# UBX_NORA_B1_SCHEM_0004_Interface_MCU.net
KiCad netlist of a schematic drawn in Altium Designer
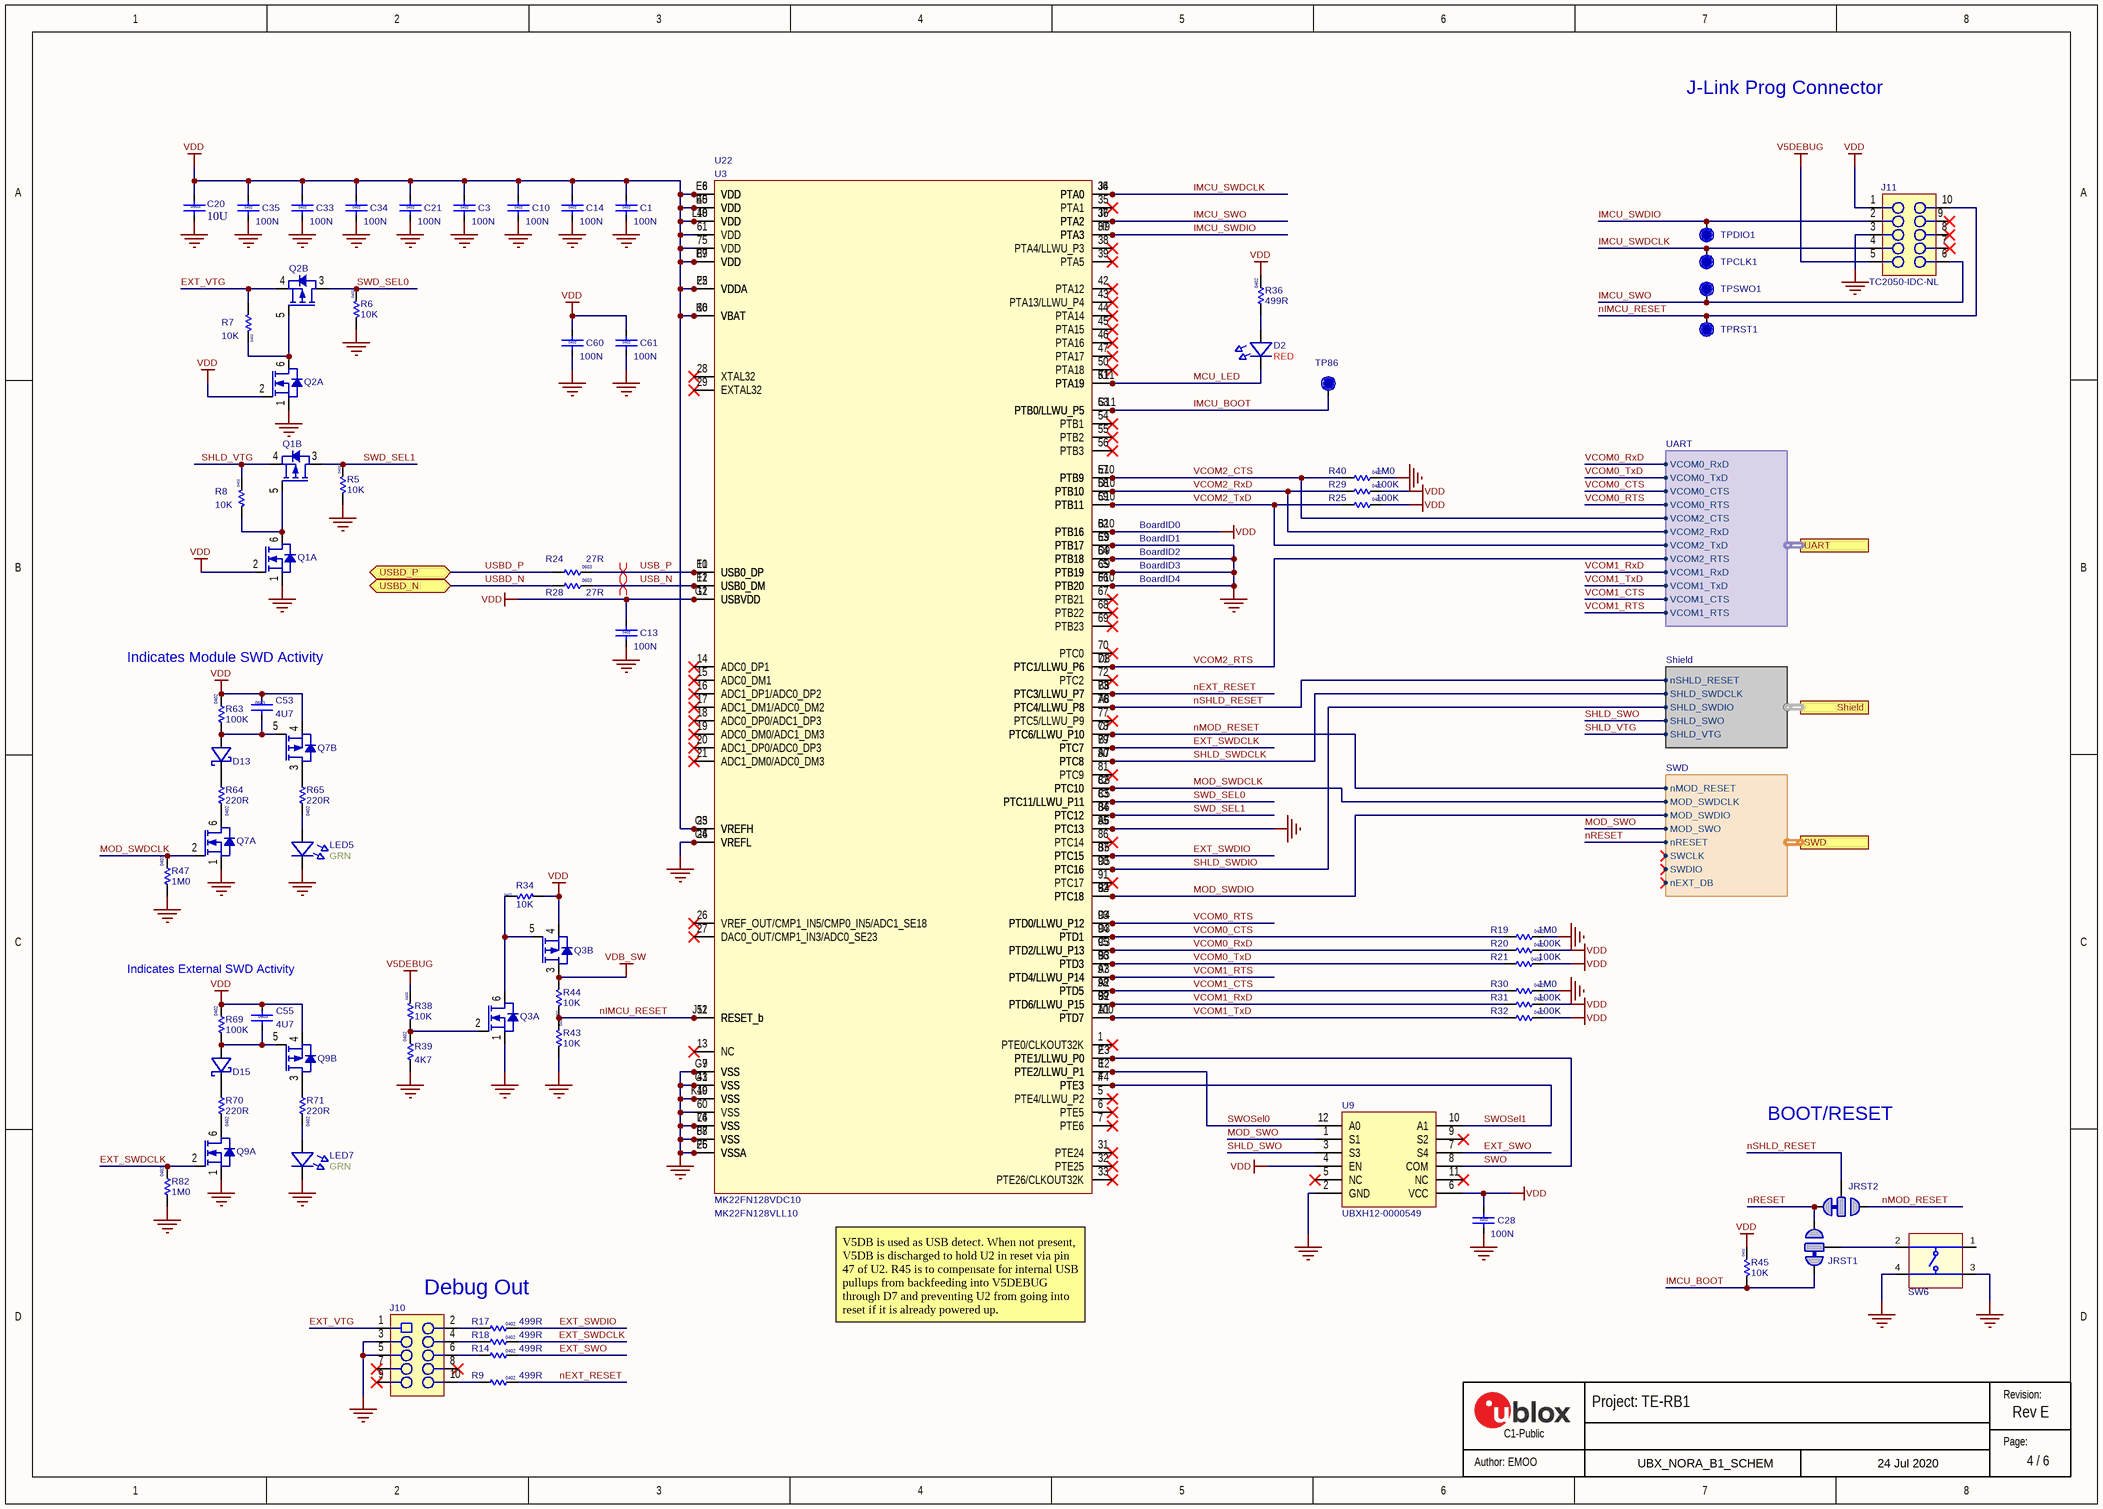
[diagram p0: UBX_NORA_B1_SCHEM_0004_Interface_MCU.SchDoc]

(export (version "E")
  (design (tool "Eeschema 10.0.6"))
  (components
    (comp (ref "C1")
      (value "100N")
      (footprint "Cap 0402 HD")
      (description "CAP CER X5R 0402 100N 10% 10V")
      (fields
        (field (name "SIZE") "0402")
        (field (name "PART NUMBER") "UBXH01-2021002")
        (field (name "TOLERANCE") "10%")
        (field (name "EDITOR") "roland.rust")
        (field (name "RELEASED BY") "roland.rust")
      )
      (libsource (lib "UBX_Parts_DB_Lib") (part "Cap Chip"))
    )
    (comp (ref "C3")
      (value "100N")
      (footprint "Cap 0402 HD")
      (description "CAP CER X5R 0402 100N 10% 10V")
      (fields
        (field (name "SIZE") "0402")
        (field (name "PART NUMBER") "UBXH01-2021002")
        (field (name "TOLERANCE") "10%")
        (field (name "EDITOR") "roland.rust")
        (field (name "RELEASED BY") "roland.rust")
      )
      (libsource (lib "UBX_Parts_DB_Lib") (part "Cap Chip"))
    )
    (comp (ref "C10")
      (value "100N")
      (footprint "Cap 0402 HD")
      (description "CAP CER X5R 0402 100N 10% 10V")
      (fields
        (field (name "SIZE") "0402")
        (field (name "PART NUMBER") "UBXH01-2021002")
        (field (name "TOLERANCE") "10%")
        (field (name "EDITOR") "roland.rust")
        (field (name "RELEASED BY") "roland.rust")
      )
      (libsource (lib "UBX_Parts_DB_Lib") (part "Cap Chip"))
    )
    (comp (ref "C13")
      (value "100N")
      (footprint "Cap 0402 HD")
      (description "CAP CER X5R 0402 100N 10% 10V")
      (fields
        (field (name "SIZE") "0402")
        (field (name "PART NUMBER") "UBXH01-2021002")
        (field (name "TOLERANCE") "10%")
        (field (name "EDITOR") "roland.rust")
        (field (name "RELEASED BY") "roland.rust")
      )
      (libsource (lib "UBX_Parts_DB_Lib") (part "Cap Chip"))
    )
    (comp (ref "C14")
      (value "100N")
      (footprint "Cap 0402 HD")
      (description "CAP CER X5R 0402 100N 10% 10V")
      (fields
        (field (name "SIZE") "0402")
        (field (name "PART NUMBER") "UBXH01-2021002")
        (field (name "TOLERANCE") "10%")
        (field (name "EDITOR") "roland.rust")
        (field (name "RELEASED BY") "roland.rust")
      )
      (libsource (lib "UBX_Parts_DB_Lib") (part "Cap Chip"))
    )
    (comp (ref "C20")
      (value "10U")
      (footprint "CAP 0603 HD")
      (description "CAP CER X5R 0603 10U 20% 10V")
      (fields
        (field (name "SIZE") "0603")
        (field (name "PART NUMBER") "UBXH01-0000040")
        (field (name "TOLERANCE") "20%")
        (field (name "EDITOR") "pierpaolo.arban")
        (field (name "RELEASED BY") "matej.budin")
      )
      (libsource (lib "UBX_Parts_DB_Lib") (part "Cap Chip"))
    )
    (comp (ref "C21")
      (value "100N")
      (footprint "Cap 0402 HD")
      (description "CAP CER X5R 0402 100N 10% 10V")
      (fields
        (field (name "SIZE") "0402")
        (field (name "PART NUMBER") "UBXH01-2021002")
        (field (name "TOLERANCE") "10%")
        (field (name "EDITOR") "roland.rust")
        (field (name "RELEASED BY") "roland.rust")
      )
      (libsource (lib "UBX_Parts_DB_Lib") (part "Cap Chip"))
    )
    (comp (ref "C28")
      (value "100N")
      (footprint "Cap 0402 HD")
      (description "CAP CER X5R 0402 100N 10% 10V")
      (fields
        (field (name "SIZE") "0402")
        (field (name "PART NUMBER") "UBXH01-2021002")
        (field (name "TOLERANCE") "10%")
        (field (name "EDITOR") "roland.rust")
        (field (name "RELEASED BY") "roland.rust")
      )
      (libsource (lib "UBX_Parts_DB_Lib") (part "Cap Chip"))
    )
    (comp (ref "C33")
      (value "100N")
      (footprint "Cap 0402 HD")
      (description "CAP CER X5R 0402 100N 10% 10V")
      (fields
        (field (name "SIZE") "0402")
        (field (name "PART NUMBER") "UBXH01-2021002")
        (field (name "TOLERANCE") "10%")
        (field (name "EDITOR") "roland.rust")
        (field (name "RELEASED BY") "roland.rust")
      )
      (libsource (lib "UBX_Parts_DB_Lib") (part "Cap Chip"))
    )
    (comp (ref "C34")
      (value "100N")
      (footprint "Cap 0402 HD")
      (description "CAP CER X5R 0402 100N 10% 10V")
      (fields
        (field (name "SIZE") "0402")
        (field (name "PART NUMBER") "UBXH01-2021002")
        (field (name "TOLERANCE") "10%")
        (field (name "EDITOR") "roland.rust")
        (field (name "RELEASED BY") "roland.rust")
      )
      (libsource (lib "UBX_Parts_DB_Lib") (part "Cap Chip"))
    )
    (comp (ref "C35")
      (value "100N")
      (footprint "Cap 0402 HD")
      (description "CAP CER X5R 0402 100N 10% 10V")
      (fields
        (field (name "SIZE") "0402")
        (field (name "PART NUMBER") "UBXH01-2021002")
        (field (name "TOLERANCE") "10%")
        (field (name "EDITOR") "roland.rust")
        (field (name "RELEASED BY") "roland.rust")
      )
      (libsource (lib "UBX_Parts_DB_Lib") (part "Cap Chip"))
    )
    (comp (ref "C53")
      (value "4U7")
      (footprint "CAP 0603 HD")
      (description "CAP CER X5R 0603 4U7 10% 6.3V")
      (fields
        (field (name "SIZE") "0603")
        (field (name "PART NUMBER") "UBXH01-2002003")
        (field (name "TOLERANCE") "10%")
        (field (name "EDITOR") "philippe.largier")
        (field (name "RELEASED BY") "roland.rust")
      )
      (libsource (lib "UBX_Parts_DB_Lib") (part "Cap Chip"))
    )
    (comp (ref "C55")
      (value "4U7")
      (footprint "CAP 0603 HD")
      (description "CAP CER X5R 0603 4U7 10% 6.3V")
      (fields
        (field (name "SIZE") "0603")
        (field (name "PART NUMBER") "UBXH01-2002003")
        (field (name "TOLERANCE") "10%")
        (field (name "EDITOR") "philippe.largier")
        (field (name "RELEASED BY") "roland.rust")
      )
      (libsource (lib "UBX_Parts_DB_Lib") (part "Cap Chip"))
    )
    (comp (ref "C60")
      (value "100N")
      (footprint "Cap 0402 HD")
      (description "CAP CER X5R 0402 100N 10% 10V")
      (fields
        (field (name "SIZE") "0402")
        (field (name "PART NUMBER") "UBXH01-2021002")
        (field (name "TOLERANCE") "10%")
        (field (name "EDITOR") "roland.rust")
        (field (name "RELEASED BY") "roland.rust")
      )
      (libsource (lib "UBX_Parts_DB_Lib") (part "Cap Chip"))
    )
    (comp (ref "C61")
      (value "100N")
      (footprint "Cap 0402 HD")
      (description "CAP CER X5R 0402 100N 10% 10V")
      (fields
        (field (name "SIZE") "0402")
        (field (name "PART NUMBER") "UBXH01-2021002")
        (field (name "TOLERANCE") "10%")
        (field (name "EDITOR") "roland.rust")
        (field (name "RELEASED BY") "roland.rust")
      )
      (libsource (lib "UBX_Parts_DB_Lib") (part "Cap Chip"))
    )
    (comp (ref "D2")
      (value "UBXH11-0000000")
      (footprint "LED_0603_RED")
      (description "LED SMD 0603 ULTRABRIGHT LITE-ON LTST-C190KRKT RED 30mA")
      (fields
        (field (name "COLOR") "RED")
        (field (name "MANUFACTURER") "Lite-on Technology Corporation")
        (field (name "EDITOR") "massimo.vlacci")
        (field (name "RELEASED BY") "sandro.sestan")
      )
      (libsource (lib "UBX_Parts_DB_Lib") (part "LED_BASE"))
    )
    (comp (ref "D13")
      (value "UBXH07-0000039")
      (footprint "SOD-523")
      (description "SCHOTTKY BARRIER DIODE 30V 200mA")
      (fields
        (field (name "MANUFACTURER") "ON Semiconductor")
        (field (name "EDITOR") "matej.budin")
        (field (name "RELEASED BY") "pierpaolo.arban")
      )
      (libsource (lib "UBX_Parts_DB_Lib") (part "Diode_Schottky"))
    )
    (comp (ref "D15")
      (value "UBXH07-0000039")
      (footprint "SOD-523")
      (description "SCHOTTKY BARRIER DIODE 30V 200mA")
      (fields
        (field (name "MANUFACTURER") "ON Semiconductor")
        (field (name "EDITOR") "matej.budin")
        (field (name "RELEASED BY") "pierpaolo.arban")
      )
      (libsource (lib "UBX_Parts_DB_Lib") (part "Diode_Schottky"))
    )
    (comp (ref "J10")
      (value "UBXH04-0000194")
      (footprint "FTSH-105-01-F-DV-K")
      (description "2-ROW SMD-PCB CONN 50MIL GRID 10 -PIN 0.41MM SQUARE 4.0MM KEYED")
      (fields
        (field (name "MANUFACTURER") "Samtec")
        (field (name "EDITOR") "par.hakansson")
        (field (name "RELEASED BY") "adam.johansson")
      )
      (libsource (lib "UBX_Parts_DB_Lib") (part "CON-10Pin_2Row"))
    )
    (comp (ref "J11")
      (value "UBXH00-0000101")
      (footprint "TC2050-IDC-NL")
      (description "TAG-CONNECT TC2050-IDC-NL 10-PIN PROBE PROGRAMMING HEADER NO LEGS TC2050-IDC-NL")
      (fields
        (field (name "MANUFACTURER P/N") "TC2050-IDC-NL")
        (field (name "MANUFACTURER") "Tag-Connect")
        (field (name "EDITOR") "eric.moog")
      )
      (libsource (lib "UBX_Parts_DB_Lib") (part "CON-10Pin_2Row_ALT"))
    )
    (comp (ref "JRST1")
      (value "UBXH00-0000083")
      (footprint "Solderbridge-Option")
      (description "SOLDERBRIDGE-OPTION")
      (fields (field (name "EDITOR") "aneeb.sohail"))
      (libsource (lib "") (part "Solderbridge-Option_1"))
    )
    (comp (ref "JRST2")
      (value "UBXH00-0000083")
      (footprint "Solderbridge-Option")
      (description "SOLDERBRIDGE-OPTION")
      (fields (field (name "EDITOR") "aneeb.sohail"))
      (libsource (lib "UBX_Parts_DB_Lib") (part "Solderbridge-Option"))
    )
    (comp (ref "LED5")
      (value "UBXH11-0000001")
      (footprint "LED_0603_GREEN")
      (description "LED SMD 0603 GREEN 2.5V 20mA")
      (fields
        (field (name "COLOR") "GRN")
        (field (name "MANUFACTURER") "Kingbright")
        (field (name "EDITOR") "gianni.falleroni")
        (field (name "RELEASED BY") "alex.claville")
      )
      (libsource (lib "UBX_Parts_DB_Lib") (part "LED_BASE"))
    )
    (comp (ref "LED7")
      (value "UBXH11-0000001")
      (footprint "LED_0603_GREEN")
      (description "LED SMD 0603 GREEN 2.5V 20mA")
      (fields
        (field (name "COLOR") "GRN")
        (field (name "MANUFACTURER") "Kingbright")
        (field (name "EDITOR") "gianni.falleroni")
        (field (name "RELEASED BY") "alex.claville")
      )
      (libsource (lib "UBX_Parts_DB_Lib") (part "LED_BASE"))
    )
    (comp (ref "Q1")
      (value "UBXH20-0000084")
      (footprint "SOT-563")
      (description "SMALL SIGNAL COMPLEMENTARY W/ ESD PROTECTION MOSFET SOT-563-6 PACKAGE")
      (fields
        (field (name "MANUFACTURER") "ON Semiconductor")
        (field (name "EDITOR") "pierpaolo.arban")
        (field (name "RELEASED BY") "matej.budin")
      )
      (libsource (lib "UBX_Parts_DB_Lib") (part "MOSFET-N-P_Pair"))
    )
    (comp (ref "Q2")
      (value "UBXH20-0000084")
      (footprint "SOT-563")
      (description "SMALL SIGNAL COMPLEMENTARY W/ ESD PROTECTION MOSFET SOT-563-6 PACKAGE")
      (fields
        (field (name "MANUFACTURER") "ON Semiconductor")
        (field (name "EDITOR") "pierpaolo.arban")
        (field (name "RELEASED BY") "matej.budin")
      )
      (libsource (lib "UBX_Parts_DB_Lib") (part "MOSFET-N-P_Pair"))
    )
    (comp (ref "Q3")
      (value "UBXH20-0000084")
      (footprint "SOT-563")
      (description "SMALL SIGNAL COMPLEMENTARY W/ ESD PROTECTION MOSFET SOT-563-6 PACKAGE")
      (fields
        (field (name "MANUFACTURER") "ON Semiconductor")
        (field (name "EDITOR") "pierpaolo.arban")
        (field (name "RELEASED BY") "matej.budin")
      )
      (libsource (lib "UBX_Parts_DB_Lib") (part "MOSFET-N-P_Pair"))
    )
    (comp (ref "Q7")
      (value "UBXH20-0000084")
      (footprint "SOT-563")
      (description "SMALL SIGNAL COMPLEMENTARY W/ ESD PROTECTION MOSFET SOT-563-6 PACKAGE")
      (fields
        (field (name "MANUFACTURER") "ON Semiconductor")
        (field (name "EDITOR") "pierpaolo.arban")
        (field (name "RELEASED BY") "matej.budin")
      )
      (libsource (lib "UBX_Parts_DB_Lib") (part "MOSFET-N-P_Pair"))
    )
    (comp (ref "Q9")
      (value "UBXH20-0000084")
      (footprint "SOT-563")
      (description "SMALL SIGNAL COMPLEMENTARY W/ ESD PROTECTION MOSFET SOT-563-6 PACKAGE")
      (fields
        (field (name "MANUFACTURER") "ON Semiconductor")
        (field (name "EDITOR") "pierpaolo.arban")
        (field (name "RELEASED BY") "matej.budin")
      )
      (libsource (lib "UBX_Parts_DB_Lib") (part "MOSFET-N-P_Pair"))
    )
    (comp (ref "R5")
      (value "10K")
      (footprint "RES 0402 HD")
      (description "RES THICK FILM CHIP 0402 10K 1% 63mW")
      (fields
        (field (name "SIZE") "0402")
        (field (name "PART NUMBER") "UBXH18-0000065")
        (field (name "TOLERANCE") "1%")
        (field (name "EDITOR") "erian.bezhani")
        (field (name "RELEASED BY") "massimo.vlacci")
      )
      (libsource (lib "UBX_Parts_DB_Lib") (part "Res sm"))
    )
    (comp (ref "R6")
      (value "10K")
      (footprint "RES 0402 HD")
      (description "RES THICK FILM CHIP 0402 10K 1% 63mW")
      (fields
        (field (name "SIZE") "0402")
        (field (name "PART NUMBER") "UBXH18-0000065")
        (field (name "TOLERANCE") "1%")
        (field (name "EDITOR") "erian.bezhani")
        (field (name "RELEASED BY") "massimo.vlacci")
      )
      (libsource (lib "UBX_Parts_DB_Lib") (part "Res sm"))
    )
    (comp (ref "R7")
      (value "10K")
      (footprint "RES 0402 HD")
      (description "RES THICK FILM CHIP 0402 10K 1% 63mW")
      (fields
        (field (name "SIZE") "0402")
        (field (name "PART NUMBER") "UBXH18-0000065")
        (field (name "TOLERANCE") "1%")
        (field (name "EDITOR") "erian.bezhani")
        (field (name "RELEASED BY") "massimo.vlacci")
      )
      (libsource (lib "UBX_Parts_DB_Lib") (part "Res sm"))
    )
    (comp (ref "R8")
      (value "10K")
      (footprint "RES 0402 HD")
      (description "RES THICK FILM CHIP 0402 10K 1% 63mW")
      (fields
        (field (name "SIZE") "0402")
        (field (name "PART NUMBER") "UBXH18-0000065")
        (field (name "TOLERANCE") "1%")
        (field (name "EDITOR") "erian.bezhani")
        (field (name "RELEASED BY") "massimo.vlacci")
      )
      (libsource (lib "UBX_Parts_DB_Lib") (part "Res sm"))
    )
    (comp (ref "R9")
      (value "499R")
      (footprint "RES 0402 HD")
      (description "RES THICK FILM CHIP 0402 499R 1% 100mW")
      (fields
        (field (name "SIZE") "0402")
        (field (name "PART NUMBER") "UBXH18-0000269")
        (field (name "TOLERANCE") "1%")
        (field (name "EDITOR") "pierpaolo.arban")
      )
      (libsource (lib "UBX_Parts_DB_Lib") (part "Res sm"))
    )
    (comp (ref "R14")
      (value "499R")
      (footprint "RES 0402 HD")
      (description "RES THICK FILM CHIP 0402 499R 1% 100mW")
      (fields
        (field (name "SIZE") "0402")
        (field (name "PART NUMBER") "UBXH18-0000269")
        (field (name "TOLERANCE") "1%")
        (field (name "EDITOR") "pierpaolo.arban")
      )
      (libsource (lib "UBX_Parts_DB_Lib") (part "Res sm"))
    )
    (comp (ref "R17")
      (value "499R")
      (footprint "RES 0402 HD")
      (description "RES THICK FILM CHIP 0402 499R 1% 100mW")
      (fields
        (field (name "SIZE") "0402")
        (field (name "PART NUMBER") "UBXH18-0000269")
        (field (name "TOLERANCE") "1%")
        (field (name "EDITOR") "pierpaolo.arban")
      )
      (libsource (lib "UBX_Parts_DB_Lib") (part "Res sm"))
    )
    (comp (ref "R18")
      (value "499R")
      (footprint "RES 0402 HD")
      (description "RES THICK FILM CHIP 0402 499R 1% 100mW")
      (fields
        (field (name "SIZE") "0402")
        (field (name "PART NUMBER") "UBXH18-0000269")
        (field (name "TOLERANCE") "1%")
        (field (name "EDITOR") "pierpaolo.arban")
      )
      (libsource (lib "UBX_Parts_DB_Lib") (part "Res sm"))
    )
    (comp (ref "R19")
      (value "1M0")
      (footprint "RES 0402 HD")
      (description "RES THICK FILM CHIP 0402 1M0 5% 63mW")
      (fields
        (field (name "SIZE") "0402")
        (field (name "PART NUMBER") "UBXH18-0008121")
        (field (name "TOLERANCE") "5%")
        (field (name "EDITOR") "daniel.hurni")
        (field (name "RELEASED BY") "doris.zahnd")
      )
      (libsource (lib "UBX_Parts_DB_Lib") (part "Res sm"))
    )
    (comp (ref "R20")
      (value "100K")
      (footprint "RES 0402 HD")
      (description "RES THICK FILM CHIP 0402 100K 1% 63mW")
      (fields
        (field (name "SIZE") "0402")
        (field (name "PART NUMBER") "UBXH18-0000005")
        (field (name "TOLERANCE") "1%")
        (field (name "EDITOR") "dario.antonaz")
        (field (name "RELEASED BY") "sandro.sestan")
      )
      (libsource (lib "UBX_Parts_DB_Lib") (part "Res sm"))
    )
    (comp (ref "R21")
      (value "100K")
      (footprint "RES 0402 HD")
      (description "RES THICK FILM CHIP 0402 100K 1% 63mW")
      (fields
        (field (name "SIZE") "0402")
        (field (name "PART NUMBER") "UBXH18-0000005")
        (field (name "TOLERANCE") "1%")
        (field (name "EDITOR") "dario.antonaz")
        (field (name "RELEASED BY") "sandro.sestan")
      )
      (libsource (lib "UBX_Parts_DB_Lib") (part "Res sm"))
    )
    (comp (ref "R24")
      (value "27R")
      (footprint "RES 0603 HD")
      (description "RES THICK FILM CHIP 0603 27R 5% 100mW")
      (fields
        (field (name "SIZE") "0603")
        (field (name "PART NUMBER") "UBXH18-0007035")
        (field (name "TOLERANCE") "5%")
        (field (name "EDITOR") "martin.frauchiger")
        (field (name "RELEASED BY") "martin.frauchiger")
      )
      (libsource (lib "UBX_Parts_DB_Lib") (part "Res sm"))
    )
    (comp (ref "R25")
      (value "100K")
      (footprint "RES 0402 HD")
      (description "RES THICK FILM CHIP 0402 100K 1% 63mW")
      (fields
        (field (name "SIZE") "0402")
        (field (name "PART NUMBER") "UBXH18-0000005")
        (field (name "TOLERANCE") "1%")
        (field (name "EDITOR") "dario.antonaz")
        (field (name "RELEASED BY") "sandro.sestan")
      )
      (libsource (lib "UBX_Parts_DB_Lib") (part "Res sm"))
    )
    (comp (ref "R28")
      (value "27R")
      (footprint "RES 0603 HD")
      (description "RES THICK FILM CHIP 0603 27R 5% 100mW")
      (fields
        (field (name "SIZE") "0603")
        (field (name "PART NUMBER") "UBXH18-0007035")
        (field (name "TOLERANCE") "5%")
        (field (name "EDITOR") "martin.frauchiger")
        (field (name "RELEASED BY") "martin.frauchiger")
      )
      (libsource (lib "UBX_Parts_DB_Lib") (part "Res sm"))
    )
    (comp (ref "R29")
      (value "100K")
      (footprint "RES 0402 HD")
      (description "RES THICK FILM CHIP 0402 100K 1% 63mW")
      (fields
        (field (name "SIZE") "0402")
        (field (name "PART NUMBER") "UBXH18-0000005")
        (field (name "TOLERANCE") "1%")
        (field (name "EDITOR") "dario.antonaz")
        (field (name "RELEASED BY") "sandro.sestan")
      )
      (libsource (lib "UBX_Parts_DB_Lib") (part "Res sm"))
    )
    (comp (ref "R30")
      (value "1M0")
      (footprint "RES 0402 HD")
      (description "RES THICK FILM CHIP 0402 1M0 5% 63mW")
      (fields
        (field (name "SIZE") "0402")
        (field (name "PART NUMBER") "UBXH18-0008121")
        (field (name "TOLERANCE") "5%")
        (field (name "EDITOR") "daniel.hurni")
        (field (name "RELEASED BY") "doris.zahnd")
      )
      (libsource (lib "UBX_Parts_DB_Lib") (part "Res sm"))
    )
    (comp (ref "R31")
      (value "100K")
      (footprint "RES 0402 HD")
      (description "RES THICK FILM CHIP 0402 100K 1% 63mW")
      (fields
        (field (name "SIZE") "0402")
        (field (name "PART NUMBER") "UBXH18-0000005")
        (field (name "TOLERANCE") "1%")
        (field (name "EDITOR") "dario.antonaz")
        (field (name "RELEASED BY") "sandro.sestan")
      )
      (libsource (lib "UBX_Parts_DB_Lib") (part "Res sm"))
    )
    (comp (ref "R32")
      (value "100K")
      (footprint "RES 0402 HD")
      (description "RES THICK FILM CHIP 0402 100K 1% 63mW")
      (fields
        (field (name "SIZE") "0402")
        (field (name "PART NUMBER") "UBXH18-0000005")
        (field (name "TOLERANCE") "1%")
        (field (name "EDITOR") "dario.antonaz")
        (field (name "RELEASED BY") "sandro.sestan")
      )
      (libsource (lib "UBX_Parts_DB_Lib") (part "Res sm"))
    )
    (comp (ref "R34")
      (value "10K")
      (footprint "RES 0402 HD")
      (description "RES THICK FILM CHIP 0402 10K 1% 63mW")
      (fields
        (field (name "SIZE") "0402")
        (field (name "PART NUMBER") "UBXH18-0000065")
        (field (name "TOLERANCE") "1%")
        (field (name "EDITOR") "erian.bezhani")
        (field (name "RELEASED BY") "massimo.vlacci")
      )
      (libsource (lib "UBX_Parts_DB_Lib") (part "Res sm"))
    )
    (comp (ref "R36")
      (value "499R")
      (footprint "RES 0402 HD")
      (description "RES THICK FILM CHIP 0402 499R 1% 100mW")
      (fields
        (field (name "SIZE") "0402")
        (field (name "PART NUMBER") "UBXH18-0000269")
        (field (name "TOLERANCE") "1%")
        (field (name "EDITOR") "pierpaolo.arban")
      )
      (libsource (lib "UBX_Parts_DB_Lib") (part "Res sm"))
    )
    (comp (ref "R38")
      (value "10K")
      (footprint "RES 0402 HD")
      (description "RES THICK FILM CHIP 0402 10K 1% 63mW")
      (fields
        (field (name "SIZE") "0402")
        (field (name "PART NUMBER") "UBXH18-0000065")
        (field (name "TOLERANCE") "1%")
        (field (name "EDITOR") "erian.bezhani")
        (field (name "RELEASED BY") "massimo.vlacci")
      )
      (libsource (lib "UBX_Parts_DB_Lib") (part "Res sm"))
    )
    (comp (ref "R39")
      (value "4K7")
      (footprint "RES 0402 HD")
      (description "RES THICK FILM CHIP 0402 4K7 1% 63mW")
      (fields
        (field (name "SIZE") "0402")
        (field (name "PART NUMBER") "UBXH18-0000213")
        (field (name "TOLERANCE") "1%")
        (field (name "EDITOR") "michael.hein")
        (field (name "RELEASED BY") "vasyl.dykyy")
      )
      (libsource (lib "UBX_Parts_DB_Lib") (part "Res sm"))
    )
    (comp (ref "R40")
      (value "1M0")
      (footprint "RES 0402 HD")
      (description "RES THICK FILM CHIP 0402 1M0 5% 63mW")
      (fields
        (field (name "SIZE") "0402")
        (field (name "PART NUMBER") "UBXH18-0008121")
        (field (name "TOLERANCE") "5%")
        (field (name "EDITOR") "daniel.hurni")
        (field (name "RELEASED BY") "doris.zahnd")
      )
      (libsource (lib "UBX_Parts_DB_Lib") (part "Res sm"))
    )
    (comp (ref "R43")
      (value "10K")
      (footprint "RES 0402 HD")
      (description "RES THICK FILM CHIP 0402 10K 1% 63mW")
      (fields
        (field (name "SIZE") "0402")
        (field (name "PART NUMBER") "UBXH18-0000065")
        (field (name "TOLERANCE") "1%")
        (field (name "EDITOR") "erian.bezhani")
        (field (name "RELEASED BY") "massimo.vlacci")
      )
      (libsource (lib "UBX_Parts_DB_Lib") (part "Res sm"))
    )
    (comp (ref "R44")
      (value "10K")
      (footprint "RES 0402 HD")
      (description "RES THICK FILM CHIP 0402 10K 1% 63mW")
      (fields
        (field (name "SIZE") "0402")
        (field (name "PART NUMBER") "UBXH18-0000065")
        (field (name "TOLERANCE") "1%")
        (field (name "EDITOR") "erian.bezhani")
        (field (name "RELEASED BY") "massimo.vlacci")
      )
      (libsource (lib "UBX_Parts_DB_Lib") (part "Res sm"))
    )
    (comp (ref "R45")
      (value "10K")
      (footprint "RES 0402 HD")
      (description "RES THICK FILM CHIP 0402 10K 1% 63mW")
      (fields
        (field (name "SIZE") "0402")
        (field (name "PART NUMBER") "UBXH18-0000065")
        (field (name "TOLERANCE") "1%")
        (field (name "EDITOR") "erian.bezhani")
        (field (name "RELEASED BY") "massimo.vlacci")
      )
      (libsource (lib "UBX_Parts_DB_Lib") (part "Res sm"))
    )
    (comp (ref "R47")
      (value "1M0")
      (footprint "RES 0402 HD")
      (description "RES THICK FILM CHIP 0402 1M0 5% 63mW")
      (fields
        (field (name "SIZE") "0402")
        (field (name "PART NUMBER") "UBXH18-0008121")
        (field (name "TOLERANCE") "5%")
        (field (name "EDITOR") "daniel.hurni")
        (field (name "RELEASED BY") "doris.zahnd")
      )
      (libsource (lib "UBX_Parts_DB_Lib") (part "Res sm"))
    )
    (comp (ref "R63")
      (value "100K")
      (footprint "RES 0402 HD")
      (description "RES THICK FILM CHIP 0402 100K 1% 63mW")
      (fields
        (field (name "SIZE") "0402")
        (field (name "PART NUMBER") "UBXH18-0000005")
        (field (name "TOLERANCE") "1%")
        (field (name "EDITOR") "dario.antonaz")
        (field (name "RELEASED BY") "sandro.sestan")
      )
      (libsource (lib "UBX_Parts_DB_Lib") (part "Res sm"))
    )
    (comp (ref "R64")
      (value "220R")
      (footprint "RES 0402 HD")
      (description "RES THICK FILM CHIP 0402 220R 5% 100mW")
      (fields
        (field (name "SIZE") "0402")
        (field (name "PART NUMBER") "UBXH18-0008033")
        (field (name "TOLERANCE") "5%")
        (field (name "EDITOR") "roland.rust")
        (field (name "RELEASED BY") "roland.rust")
      )
      (libsource (lib "UBX_Parts_DB_Lib") (part "Res sm"))
    )
    (comp (ref "R65")
      (value "220R")
      (footprint "RES 0402 HD")
      (description "RES THICK FILM CHIP 0402 220R 5% 100mW")
      (fields
        (field (name "SIZE") "0402")
        (field (name "PART NUMBER") "UBXH18-0008033")
        (field (name "TOLERANCE") "5%")
        (field (name "EDITOR") "roland.rust")
        (field (name "RELEASED BY") "roland.rust")
      )
      (libsource (lib "UBX_Parts_DB_Lib") (part "Res sm"))
    )
    (comp (ref "R69")
      (value "100K")
      (footprint "RES 0402 HD")
      (description "RES THICK FILM CHIP 0402 100K 1% 63mW")
      (fields
        (field (name "SIZE") "0402")
        (field (name "PART NUMBER") "UBXH18-0000005")
        (field (name "TOLERANCE") "1%")
        (field (name "EDITOR") "dario.antonaz")
        (field (name "RELEASED BY") "sandro.sestan")
      )
      (libsource (lib "UBX_Parts_DB_Lib") (part "Res sm"))
    )
    (comp (ref "R70")
      (value "220R")
      (footprint "RES 0402 HD")
      (description "RES THICK FILM CHIP 0402 220R 5% 100mW")
      (fields
        (field (name "SIZE") "0402")
        (field (name "PART NUMBER") "UBXH18-0008033")
        (field (name "TOLERANCE") "5%")
        (field (name "EDITOR") "roland.rust")
        (field (name "RELEASED BY") "roland.rust")
      )
      (libsource (lib "UBX_Parts_DB_Lib") (part "Res sm"))
    )
    (comp (ref "R71")
      (value "220R")
      (footprint "RES 0402 HD")
      (description "RES THICK FILM CHIP 0402 220R 5% 100mW")
      (fields
        (field (name "SIZE") "0402")
        (field (name "PART NUMBER") "UBXH18-0008033")
        (field (name "TOLERANCE") "5%")
        (field (name "EDITOR") "roland.rust")
        (field (name "RELEASED BY") "roland.rust")
      )
      (libsource (lib "UBX_Parts_DB_Lib") (part "Res sm"))
    )
    (comp (ref "R82")
      (value "1M0")
      (footprint "RES 0402 HD")
      (description "RES THICK FILM CHIP 0402 1M0 5% 63mW")
      (fields
        (field (name "SIZE") "0402")
        (field (name "PART NUMBER") "UBXH18-0008121")
        (field (name "TOLERANCE") "5%")
        (field (name "EDITOR") "daniel.hurni")
        (field (name "RELEASED BY") "doris.zahnd")
      )
      (libsource (lib "UBX_Parts_DB_Lib") (part "Res sm"))
    )
    (comp (ref "SW6")
      (value "UBXH19-0000035")
      (footprint "SW_TACT_SMT_6mm")
      (description "TACTILE SWITCH SPST SINGLE SMD")
      (fields
        (field (name "MANUFACTURER") "C&K")
        (field (name "EDITOR") "enric.suchanek")
        (field (name "RELEASED BY") "charlotte.biber")
      )
      (libsource (lib "UBX_Parts_DB_Lib") (part "SW_TACT_SPST-NO_4Pin"))
    )
    (comp (ref "TP86")
      (value "TP")
      (footprint "TP10R")
      (description "TESTPOINT 1MM CIRCULAR")
      (fields (field (name "PART NUMBER") "UBXH00-0000096") (field (name "EDITOR") "eric.moog"))
      (libsource (lib "UBX_Parts_DB_Lib") (part "TP_R"))
    )
    (comp (ref "TPCLK1")
      (value "TP")
      (footprint "TP10R")
      (description "TESTPOINT 1MM CIRCULAR")
      (fields (field (name "PART NUMBER") "UBXH00-0000096") (field (name "EDITOR") "eric.moog"))
      (libsource (lib "UBX_Parts_DB_Lib") (part "TP_R"))
    )
    (comp (ref "TPDIO1")
      (value "TP")
      (footprint "TP10R")
      (description "TESTPOINT 1MM CIRCULAR")
      (fields (field (name "PART NUMBER") "UBXH00-0000096") (field (name "EDITOR") "eric.moog"))
      (libsource (lib "UBX_Parts_DB_Lib") (part "TP_R"))
    )
    (comp (ref "TPRST1")
      (value "TP")
      (footprint "TP10R")
      (description "TESTPOINT 1MM CIRCULAR")
      (fields (field (name "PART NUMBER") "UBXH00-0000096") (field (name "EDITOR") "eric.moog"))
      (libsource (lib "UBX_Parts_DB_Lib") (part "TP_R"))
    )
    (comp (ref "TPSWO1")
      (value "TP")
      (footprint "TP10R")
      (description "TESTPOINT 1MM CIRCULAR")
      (fields (field (name "PART NUMBER") "UBXH00-0000096") (field (name "EDITOR") "eric.moog"))
      (libsource (lib "UBX_Parts_DB_Lib") (part "TP_R"))
    )
    (comp (ref "U3")
      (value "MK22FN128VLL10")
      (footprint "TSQFP50P1600X1600X160-100N")
      (description "MICROCONTROLLER IC 32-BIT 100MHZ 128KB (128K X 8) FLASH QFN")
      (fields
        (field (name "PART NUMBER") "UBXH05-0000157")
        (field (name "MANUFACTURER") "NXP")
        (field (name "PUBLISHER") "Nordic Semiconductor")
        (field (name "EDITOR") "tobias.naumann")
        (field (name "RELEASED BY") "thai.nguyen-xuan")
      )
      (libsource (lib "UBX_Parts_DB_Lib") (part "MK22FN128VLL10"))
    )
    (comp (ref "U9")
      (value "UBXH12-0000549")
      (footprint "QFN-120.5P3x3-12pin")
      (description "ANALOG SWITCH SP4T 1 CIRCUIT 2.5OHM 12-QFN (3X3) 5.5V")
      (fields
        (field (name "MANUFACTURER") "Vishay")
        (field (name "PUBLISHER") "Nordic Semiconductor")
        (field (name "EDITOR") "eric.moog")
      )
      (libsource (lib "UBX_Parts_DB_Lib") (part "DG2034EDN"))
    )
    (comp (ref "U22")
      (value "MK22FN128VDC10")
      (footprint "BGA0.5P8x8-121Pin")
      (description "MICROCONTROLLER IC 32-BIT 100MHZ 128KB (128K X 8) FLASH BGA_EVK-NORA-B1")
      (fields
        (field (name "PART NUMBER") "UBXH05-0000174")
        (field (name "MANUFACTURER") "NXP")
        (field (name "EDITOR") "eric.moog")
      )
      (libsource (lib "UBX_Parts_DB_Lib") (part "MK22FN128VDC10_EVK-NORA-B1"))
    )
  )
  (nets
    (net (code "4") (name "/EXT_SWDCLK") (class "Default")
      (node (ref "Q9") (pin "2") (pinfunction "G1_2") (pintype "passive"))
      (node (ref "R18") (pin "2") (pinfunction "2_2") (pintype "passive"))
      (node (ref "R82") (pin "2") (pinfunction "2_2") (pintype "passive"))
      (node (ref "U22") (pin "B7") (pinfunction "PTC7_B7") (pintype "passive"))
      (node (ref "U3") (pin "79") (pinfunction "PTC7_79") (pintype "passive"))
    )
    (net (code "5") (name "/EXT_SWDIO") (class "Default")
      (node (ref "R17") (pin "2") (pinfunction "2_2") (pintype "passive"))
      (node (ref "U22") (pin "B5") (pinfunction "PTC15_B5") (pintype "passive"))
      (node (ref "U3") (pin "87") (pinfunction "PTC15_87") (pintype "passive"))
    )
    (net (code "6") (name "/EXT_SWO") (class "Default")
      (node (ref "R14") (pin "2") (pinfunction "2_2") (pintype "passive"))
      (node (ref "U9") (pin "7") (pinfunction "S4_7") (pintype "passive"))
    )
    (net (code "7") (name "/EXT_VTG") (class "Default")
      (node (ref "J10") (pin "1") (pintype "passive"))
      (node (ref "Q2") (pin "4") (pinfunction "S2_4") (pintype "passive"))
      (node (ref "R7") (pin "1") (pinfunction "1_1") (pintype "passive"))
    )
    (net (code "8") (name "/IMCU_BOOT") (class "Default")
      (node (ref "JRST1") (pin "1") (pinfunction "1_1") (pintype "passive"))
      (node (ref "R45") (pin "1") (pinfunction "1_1") (pintype "passive"))
      (node (ref "TP86") (pin "1") (pintype "passive"))
      (node (ref "U22") (pin "G11") (pinfunction "PTB0/LLWU_P5_G11") (pintype "passive"))
      (node (ref "U3") (pin "53") (pinfunction "PTB0/LLWU_P5_53") (pintype "passive"))
    )
    (net (code "9") (name "/IMCU_SWDCLK") (class "Default")
      (node (ref "J11") (pin "4") (pintype "passive"))
      (node (ref "TPCLK1") (pin "1") (pintype "passive"))
      (node (ref "U22") (pin "J6") (pinfunction "PTA0_J6") (pintype "passive"))
      (node (ref "U3") (pin "34") (pinfunction "PTA0_34") (pintype "passive"))
    )
    (net (code "10") (name "/IMCU_SWDIO") (class "Default")
      (node (ref "J11") (pin "2") (pintype "passive"))
      (node (ref "TPDIO1") (pin "1") (pintype "passive"))
      (node (ref "U22") (pin "H9") (pinfunction "PTA3_H9") (pintype "passive"))
      (node (ref "U3") (pin "37") (pinfunction "PTA3_37") (pintype "passive"))
    )
    (net (code "11") (name "/IMCU_SWO") (class "Default")
      (node (ref "J11") (pin "6") (pintype "passive"))
      (node (ref "TPSWO1") (pin "1") (pintype "passive"))
      (node (ref "U22") (pin "J7") (pinfunction "PTA2_J7") (pintype "passive"))
      (node (ref "U3") (pin "36") (pinfunction "PTA2_36") (pintype "passive"))
    )
    (net (code "12") (name "/MCU_LED") (class "Default")
      (node (ref "D2") (pin "1") (pinfunction "C_1") (pintype "passive"))
      (node (ref "U22") (pin "K11") (pinfunction "PTA19_K11") (pintype "passive"))
      (node (ref "U3") (pin "51") (pinfunction "PTA19_51") (pintype "passive"))
    )
    (net (code "13") (name "/MOD_SWDCLK") (class "Default")
      (node (ref "Q7") (pin "2") (pinfunction "G1_2") (pintype "passive"))
      (node (ref "R47") (pin "2") (pinfunction "2_2") (pintype "passive"))
      (node (ref "U22") (pin "C6") (pinfunction "PTC10_C6") (pintype "passive"))
      (node (ref "U3") (pin "82") (pinfunction "PTC10_82") (pintype "passive"))
    )
    (net (code "14") (name "/MOD_SWDIO") (class "Default")
      (node (ref "U22") (pin "B4") (pinfunction "PTC18_B4") (pintype "passive"))
      (node (ref "U3") (pin "92") (pinfunction "PTC18_92") (pintype "passive"))
    )
    (net (code "15") (name "/MOD_SWO") (class "Default")
      (node (ref "U9") (pin "1") (pinfunction "S1_1") (pintype "passive"))
    )
    (net (code "16") (name "/SHLD_SWDCLK") (class "Default")
      (node (ref "U22") (pin "A7") (pinfunction "PTC8_A7") (pintype "passive"))
      (node (ref "U3") (pin "80") (pinfunction "PTC8_80") (pintype "passive"))
    )
    (net (code "17") (name "/SHLD_SWDIO") (class "Default")
      (node (ref "U22") (pin "D5") (pinfunction "PTC16_D5") (pintype "passive"))
      (node (ref "U3") (pin "90") (pinfunction "PTC16_90") (pintype "passive"))
    )
    (net (code "18") (name "/SHLD_SWO") (class "Default")
      (node (ref "U9") (pin "3") (pinfunction "S3_3") (pintype "power_in"))
    )
    (net (code "19") (name "/SHLD_VTG") (class "Default")
      (node (ref "Q1") (pin "4") (pinfunction "S2_4") (pintype "passive"))
      (node (ref "R8") (pin "2") (pinfunction "2_2") (pintype "passive"))
    )
    (net (code "20") (name "/SWD_SEL0") (class "Default")
      (node (ref "Q2") (pin "3") (pinfunction "D2_3") (pintype "passive"))
      (node (ref "R6") (pin "2") (pinfunction "2_2") (pintype "passive"))
      (node (ref "U22") (pin "C5") (pinfunction "PTC11/LLWU_P11_C5") (pintype "passive"))
      (node (ref "U3") (pin "83") (pinfunction "PTC11/LLWU_P11_83") (pintype "passive"))
    )
    (net (code "21") (name "/SWD_SEL1") (class "Default")
      (node (ref "Q1") (pin "3") (pinfunction "D2_3") (pintype "passive"))
      (node (ref "R5") (pin "2") (pinfunction "2_2") (pintype "passive"))
      (node (ref "U22") (pin "B6") (pinfunction "PTC12_B6") (pintype "passive"))
      (node (ref "U3") (pin "84") (pinfunction "PTC12_84") (pintype "passive"))
    )
    (net (code "22") (name "/SWO") (class "Default")
      (node (ref "U22") (pin "E3") (pinfunction "PTE1/LLWU_P0_E3") (pintype "passive"))
      (node (ref "U3") (pin "2") (pinfunction "PTE1/LLWU_P0_2") (pintype "passive"))
      (node (ref "U9") (pin "8") (pinfunction "COM_8") (pintype "passive"))
    )
    (net (code "23") (name "/SWOSel0") (class "Default")
      (node (ref "U22") (pin "E2") (pinfunction "PTE2/LLWU_P1_E2") (pintype "passive"))
      (node (ref "U3") (pin "3") (pinfunction "PTE2/LLWU_P1_3") (pintype "passive"))
      (node (ref "U9") (pin "12") (pinfunction "A0_12") (pintype "passive"))
    )
    (net (code "24") (name "/SWOSel1") (class "Default")
      (node (ref "U22") (pin "F4") (pinfunction "PTE3_F4") (pintype "passive"))
      (node (ref "U3") (pin "4") (pinfunction "PTE3_4") (pintype "passive"))
      (node (ref "U9") (pin "10") (pinfunction "A1_10") (pintype "passive"))
    )
    (net (code "25") (name "/USBD_N") (class "Default")
      (node (ref "R28") (pin "1") (pinfunction "1_1") (pintype "passive"))
    )
    (net (code "26") (name "/USBD_P") (class "Default")
      (node (ref "R24") (pin "1") (pinfunction "1_1") (pintype "passive"))
    )
    (net (code "27") (name "/USB_N") (class "Default")
      (node (ref "R28") (pin "2") (pinfunction "2_2") (pintype "passive"))
      (node (ref "U22") (pin "F2") (pinfunction "USB0_DM_F2") (pintype "passive"))
      (node (ref "U3") (pin "11") (pinfunction "USB0_DM_11") (pintype "passive"))
    )
    (net (code "28") (name "/USB_P") (class "Default")
      (node (ref "R24") (pin "2") (pinfunction "2_2") (pintype "passive"))
      (node (ref "U22") (pin "F1") (pinfunction "USB0_DP_F1") (pintype "passive"))
      (node (ref "U3") (pin "10") (pinfunction "USB0_DP_10") (pintype "passive"))
    )
    (net (code "29") (name "/VCOM0_CTS") (class "Default")
      (node (ref "R19") (pin "1") (pinfunction "1_1") (pintype "passive"))
      (node (ref "U22") (pin "D3") (pinfunction "PTD1_D3") (pintype "passive"))
      (node (ref "U3") (pin "94") (pinfunction "PTD1_94") (pintype "passive"))
    )
    (net (code "30") (name "/VCOM0_RTS") (class "Default")
      (node (ref "U22") (pin "D4") (pinfunction "PTD0/LLWU_P12_D4") (pintype "passive"))
      (node (ref "U3") (pin "93") (pinfunction "PTD0/LLWU_P12_93") (pintype "passive"))
    )
    (net (code "31") (name "/VCOM0_RxD") (class "Default")
      (node (ref "R20") (pin "1") (pinfunction "1_1") (pintype "passive"))
      (node (ref "U22") (pin "C3") (pinfunction "PTD2/LLWU_P13_C3") (pintype "passive"))
      (node (ref "U3") (pin "95") (pinfunction "PTD2/LLWU_P13_95") (pintype "passive"))
    )
    (net (code "32") (name "/VCOM0_TxD") (class "Default")
      (node (ref "R21") (pin "1") (pinfunction "1_1") (pintype "passive"))
      (node (ref "U22") (pin "B3") (pinfunction "PTD3_B3") (pintype "passive"))
      (node (ref "U3") (pin "96") (pinfunction "PTD3_96") (pintype "passive"))
    )
    (net (code "33") (name "/VCOM1_CTS") (class "Default")
      (node (ref "R30") (pin "1") (pinfunction "1_1") (pintype "passive"))
      (node (ref "U22") (pin "A2") (pinfunction "PTD5_A2") (pintype "passive"))
      (node (ref "U3") (pin "98") (pinfunction "PTD5_98") (pintype "passive"))
    )
    (net (code "34") (name "/VCOM1_RTS") (class "Default")
      (node (ref "U22") (pin "A3") (pinfunction "PTD4/LLWU_P14_A3") (pintype "passive"))
      (node (ref "U3") (pin "97") (pinfunction "PTD4/LLWU_P14_97") (pintype "passive"))
    )
    (net (code "35") (name "/VCOM1_RxD") (class "Default")
      (node (ref "R31") (pin "1") (pinfunction "1_1") (pintype "passive"))
      (node (ref "U22") (pin "B2") (pinfunction "PTD6/LLWU_P15_B2") (pintype "passive"))
      (node (ref "U3") (pin "99") (pinfunction "PTD6/LLWU_P15_99") (pintype "passive"))
    )
    (net (code "36") (name "/VCOM1_TxD") (class "Default")
      (node (ref "R32") (pin "1") (pinfunction "1_1") (pintype "passive"))
      (node (ref "U22") (pin "A1") (pinfunction "PTD7_A1") (pintype "passive"))
      (node (ref "U3") (pin "100") (pinfunction "PTD7_100") (pintype "passive"))
    )
    (net (code "37") (name "/VCOM2_CTS") (class "Default")
      (node (ref "R40") (pin "1") (pinfunction "1_1") (pintype "passive"))
      (node (ref "U22") (pin "E10") (pinfunction "PTB9_E10") (pintype "passive"))
      (node (ref "U3") (pin "57") (pinfunction "PTB9_57") (pintype "passive"))
    )
    (net (code "38") (name "/VCOM2_RTS") (class "Default")
      (node (ref "U22") (pin "D8") (pinfunction "PTC1/LLWU_P6_D8") (pintype "passive"))
      (node (ref "U3") (pin "71") (pinfunction "PTC1/LLWU_P6_71") (pintype "passive"))
    )
    (net (code "39") (name "/VCOM2_RxD") (class "Default")
      (node (ref "R29") (pin "1") (pinfunction "1_1") (pintype "passive"))
      (node (ref "U22") (pin "D10") (pinfunction "PTB10_D10") (pintype "passive"))
      (node (ref "U3") (pin "58") (pinfunction "PTB10_58") (pintype "passive"))
    )
    (net (code "40") (name "/VCOM2_TxD") (class "Default")
      (node (ref "R25") (pin "1") (pinfunction "1_1") (pintype "passive"))
      (node (ref "U22") (pin "C10") (pinfunction "PTB11_C10") (pintype "passive"))
      (node (ref "U3") (pin "59") (pinfunction "PTB11_59") (pintype "passive"))
    )
    (net (code "41") (name "/nEXT_RESET") (class "Default")
      (node (ref "R9") (pin "2") (pinfunction "2_2") (pintype "passive"))
      (node (ref "U22") (pin "B8") (pinfunction "PTC3/LLWU_P7_B8") (pintype "passive"))
      (node (ref "U3") (pin "73") (pinfunction "PTC3/LLWU_P7_73") (pintype "passive"))
    )
    (net (code "42") (name "/nIMCU_RESET") (class "Default")
      (node (ref "J11") (pin "10") (pintype "passive"))
      (node (ref "R43") (pin "2") (pinfunction "2_2") (pintype "passive"))
      (node (ref "R44") (pin "2") (pinfunction "2_2") (pintype "passive"))
      (node (ref "TPRST1") (pin "1") (pintype "passive"))
      (node (ref "U22") (pin "J11") (pinfunction "RESET_b_J11") (pintype "passive"))
      (node (ref "U3") (pin "52") (pinfunction "RESET_b_52") (pintype "passive"))
    )
    (net (code "43") (name "/nMOD_RESET") (class "Default")
      (node (ref "JRST2") (pin "3") (pinfunction "3_3") (pintype "passive"))
      (node (ref "U22") (pin "C7") (pinfunction "PTC6/LLWU_P10_C7") (pintype "passive"))
      (node (ref "U3") (pin "78") (pinfunction "PTC6/LLWU_P10_78") (pintype "passive"))
    )
    (net (code "44") (name "/nRESET") (class "Default")
      (node (ref "JRST1") (pin "3") (pinfunction "3_3") (pintype "passive"))
      (node (ref "JRST2") (pin "1") (pinfunction "1_1") (pintype "passive"))
    )
    (net (code "45") (name "/nSHLD_RESET") (class "Default")
      (node (ref "JRST2") (pin "2") (pinfunction "2_2") (pintype "passive"))
      (node (ref "U22") (pin "A8") (pinfunction "PTC4/LLWU_P8_A8") (pintype "passive"))
      (node (ref "U3") (pin "76") (pinfunction "PTC4/LLWU_P8_76") (pintype "passive"))
    )
    (net (code "49") (name "GND") (class "Default")
      (node (ref "C1") (pin "2") (pinfunction "2_2") (pintype "passive"))
      (node (ref "C10") (pin "2") (pinfunction "2_2") (pintype "passive"))
      (node (ref "C13") (pin "2") (pinfunction "2_2") (pintype "passive"))
      (node (ref "C14") (pin "2") (pinfunction "2_2") (pintype "passive"))
      (node (ref "C20") (pin "2") (pinfunction "2_2") (pintype "passive"))
      (node (ref "C21") (pin "2") (pinfunction "2_2") (pintype "passive"))
      (node (ref "C28") (pin "2") (pinfunction "2_2") (pintype "passive"))
      (node (ref "C3") (pin "2") (pinfunction "2_2") (pintype "passive"))
      (node (ref "C33") (pin "2") (pinfunction "2_2") (pintype "passive"))
      (node (ref "C34") (pin "2") (pinfunction "2_2") (pintype "passive"))
      (node (ref "C35") (pin "2") (pinfunction "2_2") (pintype "passive"))
      (node (ref "C60") (pin "2") (pinfunction "2_2") (pintype "passive"))
      (node (ref "C61") (pin "2") (pinfunction "2_2") (pintype "passive"))
      (node (ref "J10") (pin "3") (pintype "passive"))
      (node (ref "J10") (pin "5") (pintype "passive"))
      (node (ref "J11") (pin "3") (pintype "passive"))
      (node (ref "LED5") (pin "1") (pinfunction "C_1") (pintype "passive"))
      (node (ref "LED7") (pin "1") (pinfunction "C_1") (pintype "passive"))
      (node (ref "Q1") (pin "1") (pinfunction "S1_1") (pintype "passive"))
      (node (ref "Q2") (pin "1") (pinfunction "S1_1") (pintype "passive"))
      (node (ref "Q3") (pin "1") (pinfunction "S1_1") (pintype "passive"))
      (node (ref "Q7") (pin "1") (pinfunction "S1_1") (pintype "passive"))
      (node (ref "Q9") (pin "1") (pinfunction "S1_1") (pintype "passive"))
      (node (ref "R19") (pin "2") (pinfunction "2_2") (pintype "passive"))
      (node (ref "R30") (pin "2") (pinfunction "2_2") (pintype "passive"))
      (node (ref "R39") (pin "1") (pinfunction "1_1") (pintype "passive"))
      (node (ref "R40") (pin "2") (pinfunction "2_2") (pintype "passive"))
      (node (ref "R43") (pin "1") (pinfunction "1_1") (pintype "passive"))
      (node (ref "R47") (pin "1") (pinfunction "1_1") (pintype "passive"))
      (node (ref "R5") (pin "1") (pinfunction "1_1") (pintype "passive"))
      (node (ref "R6") (pin "1") (pinfunction "1_1") (pintype "passive"))
      (node (ref "R82") (pin "1") (pinfunction "1_1") (pintype "passive"))
      (node (ref "SW6") (pin "3") (pinfunction "3_3") (pintype "passive"))
      (node (ref "SW6") (pin "4") (pinfunction "4_4") (pintype "passive"))
      (node (ref "U22") (pin "A6") (pinfunction "PTC13_A6") (pintype "passive"))
      (node (ref "U22") (pin "C9") (pinfunction "PTB19_C9") (pintype "passive"))
      (node (ref "U22") (pin "D9") (pinfunction "PTB18_D9") (pintype "passive"))
      (node (ref "U22") (pin "E9") (pinfunction "PTB17_E9") (pintype "passive"))
      (node (ref "U22") (pin "F10") (pinfunction "PTB20_F10") (pintype "passive"))
      (node (ref "U22") (pin "F6") (pinfunction "VSSA_F6") (pintype "passive"))
      (node (ref "U22") (pin "F7") (pinfunction "VSS_F7") (pintype "passive"))
      (node (ref "U22") (pin "G3") (pinfunction "VSS_G3") (pintype "passive"))
      (node (ref "U22") (pin "G6") (pinfunction "VREFL_G6") (pintype "passive"))
      (node (ref "U22") (pin "G7") (pinfunction "VSS_G7") (pintype "passive"))
      (node (ref "U22") (pin "K10") (pinfunction "VSS_K10") (pintype "passive"))
      (node (ref "U22") (pin "L6") (pinfunction "VSS_L6") (pintype "passive"))
      (node (ref "U3") (pin "24") (pinfunction "VREFL_24") (pintype "passive"))
      (node (ref "U3") (pin "25") (pinfunction "VSSA_25") (pintype "passive"))
      (node (ref "U3") (pin "41") (pinfunction "VSS_41") (pintype "passive"))
      (node (ref "U3") (pin "49") (pinfunction "VSS_49") (pintype "passive"))
      (node (ref "U3") (pin "60") (pinfunction "VSS_60") (pintype "passive"))
      (node (ref "U3") (pin "63") (pinfunction "PTB17_63") (pintype "passive"))
      (node (ref "U3") (pin "64") (pinfunction "PTB18_64") (pintype "passive"))
      (node (ref "U3") (pin "65") (pinfunction "PTB19_65") (pintype "passive"))
      (node (ref "U3") (pin "66") (pinfunction "PTB20_66") (pintype "passive"))
      (node (ref "U3") (pin "74") (pinfunction "VSS_74") (pintype "passive"))
      (node (ref "U3") (pin "85") (pinfunction "PTC13_85") (pintype "passive"))
      (node (ref "U3") (pin "88") (pinfunction "VSS_88") (pintype "passive"))
      (node (ref "U3") (pin "9") (pinfunction "VSS_9") (pintype "passive"))
      (node (ref "U9") (pin "2") (pinfunction "GND_2") (pintype "passive"))
    )
    (net (code "50") (name "Net-(D2-A)") (class "Default")
      (node (ref "D2") (pin "2") (pinfunction "A_2") (pintype "passive"))
      (node (ref "R36") (pin "1") (pinfunction "1_1") (pintype "passive"))
    )
    (net (code "51") (name "Net-(D13-Anode)") (class "Default")
      (node (ref "C53") (pin "2") (pinfunction "2_2") (pintype "passive"))
      (node (ref "D13") (pin "A") (pinfunction "Anode_A") (pintype "passive"))
      (node (ref "Q7") (pin "5") (pinfunction "G2_5") (pintype "passive"))
      (node (ref "R63") (pin "1") (pinfunction "1_1") (pintype "passive"))
    )
    (net (code "52") (name "Net-(D13-Cathode)") (class "Default")
      (node (ref "D13") (pin "C") (pinfunction "Cathode_C") (pintype "passive"))
      (node (ref "R64") (pin "1") (pinfunction "1_1") (pintype "passive"))
    )
    (net (code "53") (name "Net-(D15-Anode)") (class "Default")
      (node (ref "C55") (pin "2") (pinfunction "2_2") (pintype "passive"))
      (node (ref "D15") (pin "A") (pinfunction "Anode_A") (pintype "passive"))
      (node (ref "Q9") (pin "5") (pinfunction "G2_5") (pintype "passive"))
      (node (ref "R69") (pin "1") (pinfunction "1_1") (pintype "passive"))
    )
    (net (code "54") (name "Net-(D15-Cathode)") (class "Default")
      (node (ref "D15") (pin "C") (pinfunction "Cathode_C") (pintype "passive"))
      (node (ref "R70") (pin "1") (pinfunction "1_1") (pintype "passive"))
    )
    (net (code "55") (name "Net-(J10-Pad2)") (class "Default")
      (node (ref "J10") (pin "2") (pintype "passive"))
      (node (ref "R17") (pin "1") (pinfunction "1_1") (pintype "passive"))
    )
    (net (code "56") (name "Net-(J10-Pad4)") (class "Default")
      (node (ref "J10") (pin "4") (pintype "passive"))
      (node (ref "R18") (pin "1") (pinfunction "1_1") (pintype "passive"))
    )
    (net (code "57") (name "Net-(J10-Pad6)") (class "Default")
      (node (ref "J10") (pin "6") (pintype "passive"))
      (node (ref "R14") (pin "1") (pinfunction "1_1") (pintype "passive"))
    )
    (net (code "58") (name "Net-(J10-Pad10)") (class "Default")
      (node (ref "J10") (pin "10") (pintype "passive"))
      (node (ref "R9") (pin "1") (pinfunction "1_1") (pintype "passive"))
    )
    (net (code "59") (name "Net-(JRST1-Pad2)") (class "Default")
      (node (ref "JRST1") (pin "2") (pinfunction "2_2") (pintype "passive"))
      (node (ref "SW6") (pin "2") (pinfunction "2_2") (pintype "passive"))
    )
    (net (code "60") (name "Net-(LED5-A)") (class "Default")
      (node (ref "LED5") (pin "2") (pinfunction "A_2") (pintype "passive"))
      (node (ref "R65") (pin "2") (pinfunction "2_2") (pintype "passive"))
    )
    (net (code "61") (name "Net-(LED7-A)") (class "Default")
      (node (ref "LED7") (pin "2") (pinfunction "A_2") (pintype "passive"))
      (node (ref "R71") (pin "2") (pinfunction "2_2") (pintype "passive"))
    )
    (net (code "62") (name "Net-(Q1A-D1)") (class "Default")
      (node (ref "Q1") (pin "5") (pinfunction "G2_5") (pintype "passive"))
      (node (ref "Q1") (pin "6") (pinfunction "D1_6") (pintype "passive"))
      (node (ref "R8") (pin "1") (pinfunction "1_1") (pintype "passive"))
    )
    (net (code "63") (name "Net-(Q2A-D1)") (class "Default")
      (node (ref "Q2") (pin "5") (pinfunction "G2_5") (pintype "passive"))
      (node (ref "Q2") (pin "6") (pinfunction "D1_6") (pintype "passive"))
      (node (ref "R7") (pin "2") (pinfunction "2_2") (pintype "passive"))
    )
    (net (code "64") (name "Net-(Q3A-D1)") (class "Default")
      (node (ref "Q3") (pin "5") (pinfunction "G2_5") (pintype "passive"))
      (node (ref "Q3") (pin "6") (pinfunction "D1_6") (pintype "passive"))
      (node (ref "R34") (pin "2") (pinfunction "2_2") (pintype "passive"))
    )
    (net (code "65") (name "Net-(Q3A-G1)") (class "Default")
      (node (ref "Q3") (pin "2") (pinfunction "G1_2") (pintype "passive"))
      (node (ref "R38") (pin "1") (pinfunction "1_1") (pintype "passive"))
      (node (ref "R39") (pin "2") (pinfunction "2_2") (pintype "passive"))
    )
    (net (code "66") (name "Net-(Q7A-D1)") (class "Default")
      (node (ref "Q7") (pin "6") (pinfunction "D1_6") (pintype "passive"))
      (node (ref "R64") (pin "2") (pinfunction "2_2") (pintype "passive"))
    )
    (net (code "67") (name "Net-(Q7B-D2)") (class "Default")
      (node (ref "Q7") (pin "3") (pinfunction "D2_3") (pintype "passive"))
      (node (ref "R65") (pin "1") (pinfunction "1_1") (pintype "passive"))
    )
    (net (code "68") (name "Net-(Q9A-D1)") (class "Default")
      (node (ref "Q9") (pin "6") (pinfunction "D1_6") (pintype "passive"))
      (node (ref "R70") (pin "2") (pinfunction "2_2") (pintype "passive"))
    )
    (net (code "69") (name "Net-(Q9B-D2)") (class "Default")
      (node (ref "Q9") (pin "3") (pinfunction "D2_3") (pintype "passive"))
      (node (ref "R71") (pin "1") (pinfunction "1_1") (pintype "passive"))
    )
    (net (code "70") (name "V5DEBUG") (class "Default")
      (node (ref "J11") (pin "5") (pintype "passive"))
      (node (ref "R38") (pin "2") (pinfunction "2_2") (pintype "passive"))
    )
    (net (code "71") (name "VDB_SW") (class "Default")
      (node (ref "Q3") (pin "3") (pinfunction "D2_3") (pintype "passive"))
      (node (ref "R44") (pin "1") (pinfunction "1_1") (pintype "passive"))
    )
    (net (code "72") (name "VDD") (class "Default")
      (node (ref "C1") (pin "1") (pinfunction "1_1") (pintype "passive"))
      (node (ref "C10") (pin "1") (pinfunction "1_1") (pintype "passive"))
      (node (ref "C13") (pin "1") (pinfunction "1_1") (pintype "passive"))
      (node (ref "C14") (pin "1") (pinfunction "1_1") (pintype "passive"))
      (node (ref "C20") (pin "1") (pinfunction "1_1") (pintype "passive"))
      (node (ref "C21") (pin "1") (pinfunction "1_1") (pintype "passive"))
      (node (ref "C28") (pin "1") (pinfunction "1_1") (pintype "passive"))
      (node (ref "C3") (pin "1") (pinfunction "1_1") (pintype "passive"))
      (node (ref "C33") (pin "1") (pinfunction "1_1") (pintype "passive"))
      (node (ref "C34") (pin "1") (pinfunction "1_1") (pintype "passive"))
      (node (ref "C35") (pin "1") (pinfunction "1_1") (pintype "passive"))
      (node (ref "C53") (pin "1") (pinfunction "1_1") (pintype "passive"))
      (node (ref "C55") (pin "1") (pinfunction "1_1") (pintype "passive"))
      (node (ref "C60") (pin "1") (pinfunction "1_1") (pintype "passive"))
      (node (ref "C61") (pin "1") (pinfunction "1_1") (pintype "passive"))
      (node (ref "J11") (pin "1") (pintype "passive"))
      (node (ref "Q1") (pin "2") (pinfunction "G1_2") (pintype "passive"))
      (node (ref "Q2") (pin "2") (pinfunction "G1_2") (pintype "passive"))
      (node (ref "Q3") (pin "4") (pinfunction "S2_4") (pintype "passive"))
      (node (ref "Q7") (pin "4") (pinfunction "S2_4") (pintype "passive"))
      (node (ref "Q9") (pin "4") (pinfunction "S2_4") (pintype "passive"))
      (node (ref "R20") (pin "2") (pinfunction "2_2") (pintype "passive"))
      (node (ref "R21") (pin "2") (pinfunction "2_2") (pintype "passive"))
      (node (ref "R25") (pin "2") (pinfunction "2_2") (pintype "passive"))
      (node (ref "R29") (pin "2") (pinfunction "2_2") (pintype "passive"))
      (node (ref "R31") (pin "2") (pinfunction "2_2") (pintype "passive"))
      (node (ref "R32") (pin "2") (pinfunction "2_2") (pintype "passive"))
      (node (ref "R34") (pin "1") (pinfunction "1_1") (pintype "passive"))
      (node (ref "R36") (pin "2") (pinfunction "2_2") (pintype "passive"))
      (node (ref "R45") (pin "2") (pinfunction "2_2") (pintype "passive"))
      (node (ref "R63") (pin "2") (pinfunction "2_2") (pintype "passive"))
      (node (ref "R69") (pin "2") (pinfunction "2_2") (pintype "passive"))
      (node (ref "U22") (pin "B10") (pinfunction "PTB16_B10") (pintype "passive"))
      (node (ref "U22") (pin "E5") (pinfunction "VDD_E5") (pintype "passive"))
      (node (ref "U22") (pin "E6") (pinfunction "VDD_E6") (pintype "passive"))
      (node (ref "U22") (pin "E7") (pinfunction "VDD_E7") (pintype "passive"))
      (node (ref "U22") (pin "F5") (pinfunction "VDDA_F5") (pintype "passive"))
      (node (ref "U22") (pin "G1") (pinfunction "USBVDD_G1") (pintype "passive"))
      (node (ref "U22") (pin "G5") (pinfunction "VREFH_G5") (pintype "passive"))
      (node (ref "U22") (pin "K6") (pinfunction "VBAT_K6") (pintype "passive"))
      (node (ref "U22") (pin "L10") (pinfunction "VDD_L10") (pintype "passive"))
      (node (ref "U3") (pin "12") (pinfunction "USBVDD_12") (pintype "passive"))
      (node (ref "U3") (pin "22") (pinfunction "VDDA_22") (pintype "passive"))
      (node (ref "U3") (pin "23") (pinfunction "VREFH_23") (pintype "passive"))
      (node (ref "U3") (pin "30") (pinfunction "VBAT_30") (pintype "passive"))
      (node (ref "U3") (pin "40") (pinfunction "VDD_40") (pintype "passive"))
      (node (ref "U3") (pin "48") (pinfunction "VDD_48") (pintype "passive"))
      (node (ref "U3") (pin "61") (pinfunction "VDD_61") (pintype "passive"))
      (node (ref "U3") (pin "62") (pinfunction "PTB16_62") (pintype "passive"))
      (node (ref "U3") (pin "75") (pinfunction "VDD_75") (pintype "passive"))
      (node (ref "U3") (pin "8") (pinfunction "VDD_8") (pintype "passive"))
      (node (ref "U3") (pin "89") (pinfunction "VDD_89") (pintype "passive"))
      (node (ref "U9") (pin "4") (pinfunction "EN_4") (pintype "passive"))
      (node (ref "U9") (pin "6") (pinfunction "VCC_6") (pintype "power_in"))
    )
    (net (code "73") (name "unconnected-(J10-Pad7)") (class "Default")
      (node (ref "J10") (pin "7") (pintype "passive"))
    )
    (net (code "74") (name "unconnected-(J10-Pad8)") (class "Default")
      (node (ref "J10") (pin "8") (pintype "passive+no_connect"))
    )
    (net (code "75") (name "unconnected-(J10-Pad9)") (class "Default")
      (node (ref "J10") (pin "9") (pintype "passive"))
    )
    (net (code "76") (name "unconnected-(J11-Pad7)") (class "Default")
      (node (ref "J11") (pin "7") (pintype "passive+no_connect"))
    )
    (net (code "77") (name "unconnected-(J11-Pad8)") (class "Default")
      (node (ref "J11") (pin "8") (pintype "passive"))
    )
    (net (code "78") (name "unconnected-(J11-Pad9)") (class "Default")
      (node (ref "J11") (pin "9") (pintype "passive"))
    )
    (net (code "79") (name "unconnected-(SW6-Pad1)") (class "Default")
      (node (ref "SW6") (pin "1") (pinfunction "1_1") (pintype "passive"))
    )
    (net (code "80") (name "unconnected-(U3-ADC0_DM0{slash}ADC1_DM3-Pad19)") (class "Default")
      (node (ref "U3") (pin "19") (pinfunction "ADC0_DM0/ADC1_DM3_19") (pintype "passive+no_connect"))
    )
    (net (code "81") (name "unconnected-(U3-ADC0_DM1-Pad15)") (class "Default")
      (node (ref "U3") (pin "15") (pinfunction "ADC0_DM1_15") (pintype "passive+no_connect"))
    )
    (net (code "82") (name "unconnected-(U3-ADC0_DP0{slash}ADC1_DP3-Pad18)") (class "Default")
      (node (ref "U3") (pin "18") (pinfunction "ADC0_DP0/ADC1_DP3_18") (pintype "passive+no_connect"))
    )
    (net (code "83") (name "unconnected-(U3-ADC0_DP1-Pad14)") (class "Default")
      (node (ref "U3") (pin "14") (pinfunction "ADC0_DP1_14") (pintype "passive+no_connect"))
    )
    (net (code "84") (name "unconnected-(U3-ADC1_DM0{slash}ADC0_DM3-Pad21)") (class "Default")
      (node (ref "U3") (pin "21") (pinfunction "ADC1_DM0/ADC0_DM3_21") (pintype "passive+no_connect"))
    )
    (net (code "85") (name "unconnected-(U3-ADC1_DM1{slash}ADC0_DM2-Pad17)") (class "Default")
      (node (ref "U3") (pin "17") (pinfunction "ADC1_DM1/ADC0_DM2_17") (pintype "passive+no_connect"))
    )
    (net (code "86") (name "unconnected-(U3-ADC1_DP0{slash}ADC0_DP3-Pad20)") (class "Default")
      (node (ref "U3") (pin "20") (pinfunction "ADC1_DP0/ADC0_DP3_20") (pintype "passive+no_connect"))
    )
    (net (code "87") (name "unconnected-(U3-ADC1_DP1{slash}ADC0_DP2-Pad16)") (class "Default")
      (node (ref "U3") (pin "16") (pinfunction "ADC1_DP1/ADC0_DP2_16") (pintype "passive+no_connect"))
    )
    (net (code "88") (name "unconnected-(U3-DAC0_OUT{slash}CMP1_IN3{slash}ADC0_SE23-Pad27)") (class "Default")
      (node (ref "U3") (pin "27") (pinfunction "DAC0_OUT/CMP1_IN3/ADC0_SE23_27") (pintype "passive+no_connect"))
    )
    (net (code "89") (name "unconnected-(U3-EXTAL32-Pad29)") (class "Default")
      (node (ref "U3") (pin "29") (pinfunction "EXTAL32_29") (pintype "passive+no_connect"))
    )
    (net (code "90") (name "unconnected-(U3-NC-Pad13)") (class "Default")
      (node (ref "U3") (pin "13") (pinfunction "NC_13") (pintype "passive+no_connect"))
    )
    (net (code "91") (name "unconnected-(U3-PTA1-Pad35)") (class "Default")
      (node (ref "U3") (pin "35") (pinfunction "PTA1_35") (pintype "passive+no_connect"))
    )
    (net (code "92") (name "unconnected-(U3-PTA4{slash}LLWU_P3-Pad38)") (class "Default")
      (node (ref "U3") (pin "38") (pinfunction "PTA4/LLWU_P3_38") (pintype "passive+no_connect"))
    )
    (net (code "93") (name "unconnected-(U3-PTA5-Pad39)") (class "Default")
      (node (ref "U3") (pin "39") (pinfunction "PTA5_39") (pintype "passive+no_connect"))
    )
    (net (code "94") (name "unconnected-(U3-PTA12-Pad42)") (class "Default")
      (node (ref "U3") (pin "42") (pinfunction "PTA12_42") (pintype "passive+no_connect"))
    )
    (net (code "95") (name "unconnected-(U3-PTA13{slash}LLWU_P4-Pad43)") (class "Default")
      (node (ref "U3") (pin "43") (pinfunction "PTA13/LLWU_P4_43") (pintype "passive+no_connect"))
    )
    (net (code "96") (name "unconnected-(U3-PTA14-Pad44)") (class "Default")
      (node (ref "U3") (pin "44") (pinfunction "PTA14_44") (pintype "passive+no_connect"))
    )
    (net (code "97") (name "unconnected-(U3-PTA15-Pad45)") (class "Default")
      (node (ref "U3") (pin "45") (pinfunction "PTA15_45") (pintype "passive+no_connect"))
    )
    (net (code "98") (name "unconnected-(U3-PTA16-Pad46)") (class "Default")
      (node (ref "U3") (pin "46") (pinfunction "PTA16_46") (pintype "passive+no_connect"))
    )
    (net (code "99") (name "unconnected-(U3-PTA17-Pad47)") (class "Default")
      (node (ref "U3") (pin "47") (pinfunction "PTA17_47") (pintype "passive+no_connect"))
    )
    (net (code "100") (name "unconnected-(U3-PTA18-Pad50)") (class "Default")
      (node (ref "U3") (pin "50") (pinfunction "PTA18_50") (pintype "passive+no_connect"))
    )
    (net (code "101") (name "unconnected-(U3-PTB1-Pad54)") (class "Default")
      (node (ref "U3") (pin "54") (pinfunction "PTB1_54") (pintype "passive+no_connect"))
    )
    (net (code "102") (name "unconnected-(U3-PTB2-Pad55)") (class "Default")
      (node (ref "U3") (pin "55") (pinfunction "PTB2_55") (pintype "passive+no_connect"))
    )
    (net (code "103") (name "unconnected-(U3-PTB3-Pad56)") (class "Default")
      (node (ref "U3") (pin "56") (pinfunction "PTB3_56") (pintype "passive+no_connect"))
    )
    (net (code "104") (name "unconnected-(U3-PTB21-Pad67)") (class "Default")
      (node (ref "U3") (pin "67") (pinfunction "PTB21_67") (pintype "passive+no_connect"))
    )
    (net (code "105") (name "unconnected-(U3-PTB22-Pad68)") (class "Default")
      (node (ref "U3") (pin "68") (pinfunction "PTB22_68") (pintype "passive+no_connect"))
    )
    (net (code "106") (name "unconnected-(U3-PTB23-Pad69)") (class "Default")
      (node (ref "U3") (pin "69") (pinfunction "PTB23_69") (pintype "passive+no_connect"))
    )
    (net (code "107") (name "unconnected-(U3-PTC0-Pad70)") (class "Default")
      (node (ref "U3") (pin "70") (pinfunction "PTC0_70") (pintype "passive+no_connect"))
    )
    (net (code "108") (name "unconnected-(U3-PTC2-Pad72)") (class "Default")
      (node (ref "U3") (pin "72") (pinfunction "PTC2_72") (pintype "passive+no_connect"))
    )
    (net (code "109") (name "unconnected-(U3-PTC5{slash}LLWU_P9-Pad77)") (class "Default")
      (node (ref "U3") (pin "77") (pinfunction "PTC5/LLWU_P9_77") (pintype "passive+no_connect"))
    )
    (net (code "110") (name "unconnected-(U3-PTC9-Pad81)") (class "Default")
      (node (ref "U3") (pin "81") (pinfunction "PTC9_81") (pintype "passive+no_connect"))
    )
    (net (code "111") (name "unconnected-(U3-PTC14-Pad86)") (class "Default")
      (node (ref "U3") (pin "86") (pinfunction "PTC14_86") (pintype "passive+no_connect"))
    )
    (net (code "112") (name "unconnected-(U3-PTC17-Pad91)") (class "Default")
      (node (ref "U3") (pin "91") (pinfunction "PTC17_91") (pintype "passive+no_connect"))
    )
    (net (code "113") (name "unconnected-(U3-PTE0{slash}CLKOUT32K-Pad1)") (class "Default")
      (node (ref "U3") (pin "1") (pinfunction "PTE0/CLKOUT32K_1") (pintype "passive+no_connect"))
    )
    (net (code "114") (name "unconnected-(U3-PTE4{slash}LLWU_P2-Pad5)") (class "Default")
      (node (ref "U3") (pin "5") (pinfunction "PTE4/LLWU_P2_5") (pintype "passive+no_connect"))
    )
    (net (code "115") (name "unconnected-(U3-PTE5-Pad6)") (class "Default")
      (node (ref "U3") (pin "6") (pinfunction "PTE5_6") (pintype "passive+no_connect"))
    )
    (net (code "116") (name "unconnected-(U3-PTE6-Pad7)") (class "Default")
      (node (ref "U3") (pin "7") (pinfunction "PTE6_7") (pintype "passive+no_connect"))
    )
    (net (code "117") (name "unconnected-(U3-PTE24-Pad31)") (class "Default")
      (node (ref "U3") (pin "31") (pinfunction "PTE24_31") (pintype "passive+no_connect"))
    )
    (net (code "118") (name "unconnected-(U3-PTE25-Pad32)") (class "Default")
      (node (ref "U3") (pin "32") (pinfunction "PTE25_32") (pintype "passive+no_connect"))
    )
    (net (code "119") (name "unconnected-(U3-PTE26{slash}CLKOUT32K-Pad33)") (class "Default")
      (node (ref "U3") (pin "33") (pinfunction "PTE26/CLKOUT32K_33") (pintype "passive+no_connect"))
    )
    (net (code "120") (name "unconnected-(U3-VREF_OUT{slash}CMP1_IN5{slash}CMP0_IN5{slash}ADC1_SE18-Pad26)") (class "Default")
      (node (ref "U3") (pin "26") (pinfunction "VREF_OUT/CMP1_IN5/CMP0_IN5/ADC1_SE18_26") (pintype "passive+no_connect"))
    )
    (net (code "121") (name "unconnected-(U3-XTAL32-Pad28)") (class "Default")
      (node (ref "U3") (pin "28") (pinfunction "XTAL32_28") (pintype "passive+no_connect"))
    )
    (net (code "122") (name "unconnected-(U9-NC-Pad5)") (class "Default")
      (node (ref "U9") (pin "5") (pinfunction "NC_5") (pintype "passive+no_connect"))
    )
    (net (code "123") (name "unconnected-(U9-NC-Pad11)") (class "Default")
      (node (ref "U9") (pin "11") (pinfunction "NC_11") (pintype "passive+no_connect"))
    )
    (net (code "124") (name "unconnected-(U9-S2-Pad9)") (class "Default")
      (node (ref "U9") (pin "9") (pinfunction "S2_9") (pintype "passive+no_connect"))
    )
  )
)
